# ui.net
KiCad netlist of a schematic drawn in EAGLE
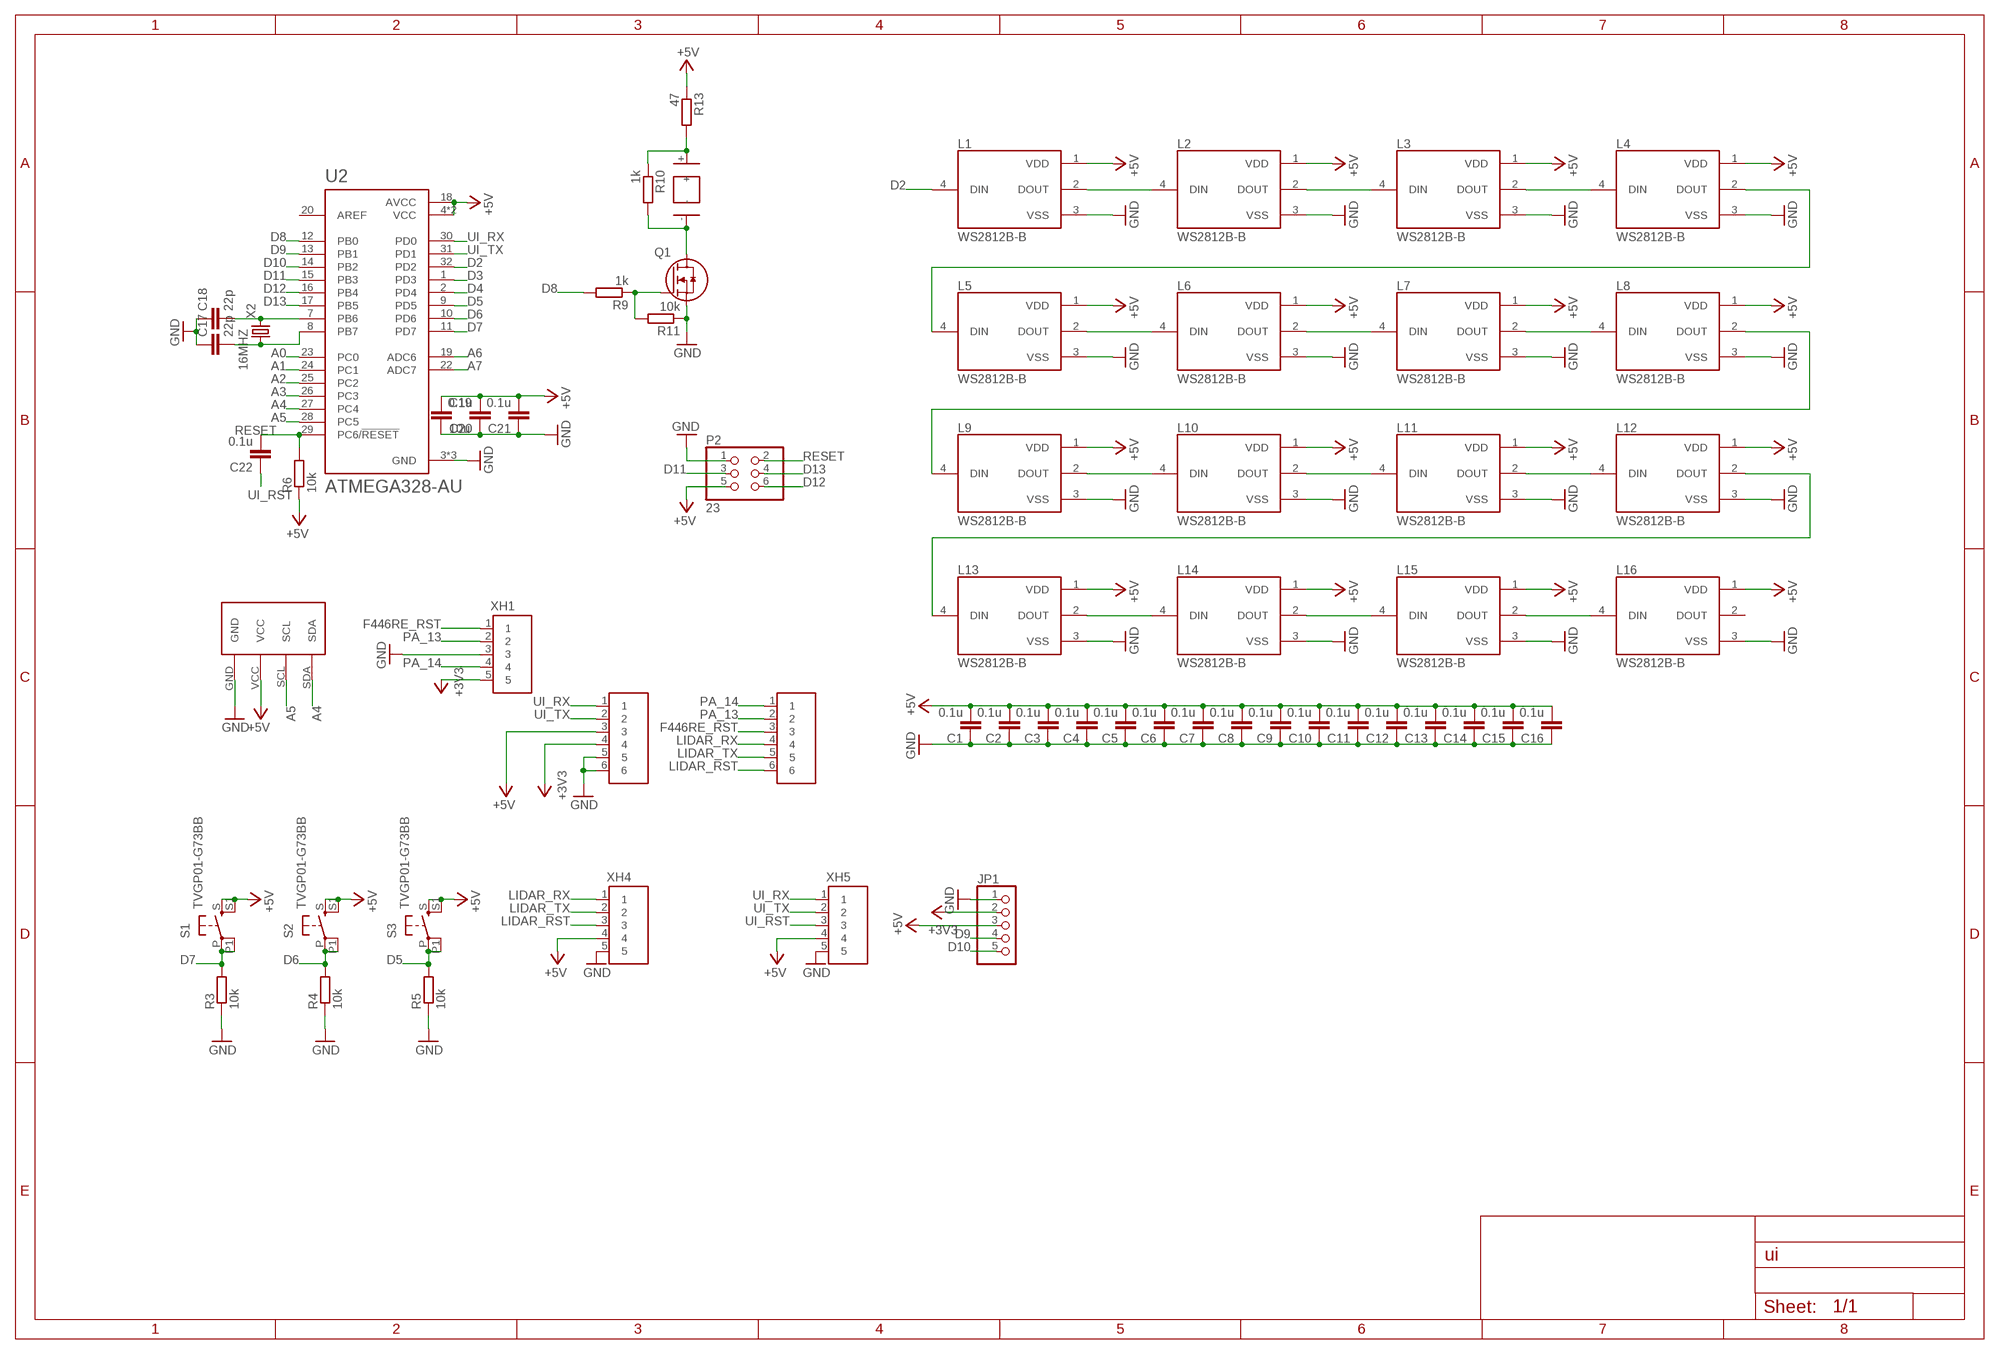
[diagram p0: schematic, sheet 1]

(export (version "E")
  (design (tool "Eeschema 10.0.6"))
  (components
    (comp (ref "B1")
      (value "PKLCS1212E4001-R1")
      (footprint "eagle-import:PKLCS1212E4001-R1")
      (libsource (lib "eagle-import") (part "PKLCS1212E4001-R1"))
    )
    (comp (ref "C1")
      (value "0.1u")
      (footprint "eagle-import:C0603")
      (libsource (lib "eagle-import") (part "C-EUC0603"))
    )
    (comp (ref "C2")
      (value "0.1u")
      (footprint "eagle-import:C0603")
      (libsource (lib "eagle-import") (part "C-EUC0603"))
    )
    (comp (ref "C3")
      (value "0.1u")
      (footprint "eagle-import:C0603")
      (libsource (lib "eagle-import") (part "C-EUC0603"))
    )
    (comp (ref "C4")
      (value "0.1u")
      (footprint "eagle-import:C0603")
      (libsource (lib "eagle-import") (part "C-EUC0603"))
    )
    (comp (ref "C5")
      (value "0.1u")
      (footprint "eagle-import:C0603")
      (libsource (lib "eagle-import") (part "C-EUC0603"))
    )
    (comp (ref "C6")
      (value "0.1u")
      (footprint "eagle-import:C0603")
      (libsource (lib "eagle-import") (part "C-EUC0603"))
    )
    (comp (ref "C7")
      (value "0.1u")
      (footprint "eagle-import:C0603")
      (libsource (lib "eagle-import") (part "C-EUC0603"))
    )
    (comp (ref "C8")
      (value "0.1u")
      (footprint "eagle-import:C0603")
      (libsource (lib "eagle-import") (part "C-EUC0603"))
    )
    (comp (ref "C9")
      (value "0.1u")
      (footprint "eagle-import:C0603")
      (libsource (lib "eagle-import") (part "C-EUC0603"))
    )
    (comp (ref "C10")
      (value "0.1u")
      (footprint "eagle-import:C0603")
      (libsource (lib "eagle-import") (part "C-EUC0603"))
    )
    (comp (ref "C11")
      (value "0.1u")
      (footprint "eagle-import:C0603")
      (libsource (lib "eagle-import") (part "C-EUC0603"))
    )
    (comp (ref "C12")
      (value "0.1u")
      (footprint "eagle-import:C0603")
      (libsource (lib "eagle-import") (part "C-EUC0603"))
    )
    (comp (ref "C13")
      (value "0.1u")
      (footprint "eagle-import:C0603")
      (libsource (lib "eagle-import") (part "C-EUC0603"))
    )
    (comp (ref "C14")
      (value "0.1u")
      (footprint "eagle-import:C0603")
      (libsource (lib "eagle-import") (part "C-EUC0603"))
    )
    (comp (ref "C15")
      (value "0.1u")
      (footprint "eagle-import:C0603")
      (libsource (lib "eagle-import") (part "C-EUC0603"))
    )
    (comp (ref "C16")
      (value "0.1u")
      (footprint "eagle-import:C0603")
      (libsource (lib "eagle-import") (part "C-EUC0603"))
    )
    (comp (ref "C17")
      (value "22p")
      (footprint "eagle-import:C0603")
      (libsource (lib "eagle-import") (part "C-EUC0603"))
    )
    (comp (ref "C18")
      (value "22p")
      (footprint "eagle-import:C0603")
      (libsource (lib "eagle-import") (part "C-EUC0603"))
    )
    (comp (ref "C19")
      (value "10u")
      (footprint "eagle-import:C0805")
      (libsource (lib "eagle-import") (part "C-EUC0805"))
    )
    (comp (ref "C20")
      (value "0.1u")
      (footprint "eagle-import:C0603")
      (libsource (lib "eagle-import") (part "C-EUC0603"))
    )
    (comp (ref "C21")
      (value "0.1u")
      (footprint "eagle-import:C0603")
      (libsource (lib "eagle-import") (part "C-EUC0603"))
    )
    (comp (ref "C22")
      (value "0.1u")
      (footprint "eagle-import:C0603")
      (libsource (lib "eagle-import") (part "C-EUC0603"))
    )
    (comp (ref "JP1")
      (value "PINHD-1X5")
      (footprint "eagle-import:1X05")
      (libsource (lib "eagle-import") (part "PINHD-1X5"))
    )
    (comp (ref "L1")
      (value "WS2812B-B")
      (footprint "eagle-import:LED_WS2812B-B")
      (fields (field (name "MF") "Worldsemi"))
      (libsource (lib "eagle-import") (part "WS2812B-B"))
    )
    (comp (ref "L2")
      (value "WS2812B-B")
      (footprint "eagle-import:LED_WS2812B-B")
      (fields (field (name "MF") "Worldsemi"))
      (libsource (lib "eagle-import") (part "WS2812B-B"))
    )
    (comp (ref "L3")
      (value "WS2812B-B")
      (footprint "eagle-import:LED_WS2812B-B")
      (fields (field (name "MF") "Worldsemi"))
      (libsource (lib "eagle-import") (part "WS2812B-B"))
    )
    (comp (ref "L4")
      (value "WS2812B-B")
      (footprint "eagle-import:LED_WS2812B-B")
      (fields (field (name "MF") "Worldsemi"))
      (libsource (lib "eagle-import") (part "WS2812B-B"))
    )
    (comp (ref "L5")
      (value "WS2812B-B")
      (footprint "eagle-import:LED_WS2812B-B")
      (fields (field (name "MF") "Worldsemi"))
      (libsource (lib "eagle-import") (part "WS2812B-B"))
    )
    (comp (ref "L6")
      (value "WS2812B-B")
      (footprint "eagle-import:LED_WS2812B-B")
      (fields (field (name "MF") "Worldsemi"))
      (libsource (lib "eagle-import") (part "WS2812B-B"))
    )
    (comp (ref "L7")
      (value "WS2812B-B")
      (footprint "eagle-import:LED_WS2812B-B")
      (fields (field (name "MF") "Worldsemi"))
      (libsource (lib "eagle-import") (part "WS2812B-B"))
    )
    (comp (ref "L8")
      (value "WS2812B-B")
      (footprint "eagle-import:LED_WS2812B-B")
      (fields (field (name "MF") "Worldsemi"))
      (libsource (lib "eagle-import") (part "WS2812B-B"))
    )
    (comp (ref "L9")
      (value "WS2812B-B")
      (footprint "eagle-import:LED_WS2812B-B")
      (fields (field (name "MF") "Worldsemi"))
      (libsource (lib "eagle-import") (part "WS2812B-B"))
    )
    (comp (ref "L10")
      (value "WS2812B-B")
      (footprint "eagle-import:LED_WS2812B-B")
      (fields (field (name "MF") "Worldsemi"))
      (libsource (lib "eagle-import") (part "WS2812B-B"))
    )
    (comp (ref "L11")
      (value "WS2812B-B")
      (footprint "eagle-import:LED_WS2812B-B")
      (fields (field (name "MF") "Worldsemi"))
      (libsource (lib "eagle-import") (part "WS2812B-B"))
    )
    (comp (ref "L12")
      (value "WS2812B-B")
      (footprint "eagle-import:LED_WS2812B-B")
      (fields (field (name "MF") "Worldsemi"))
      (libsource (lib "eagle-import") (part "WS2812B-B"))
    )
    (comp (ref "L13")
      (value "WS2812B-B")
      (footprint "eagle-import:LED_WS2812B-B")
      (fields (field (name "MF") "Worldsemi"))
      (libsource (lib "eagle-import") (part "WS2812B-B"))
    )
    (comp (ref "L14")
      (value "WS2812B-B")
      (footprint "eagle-import:LED_WS2812B-B")
      (fields (field (name "MF") "Worldsemi"))
      (libsource (lib "eagle-import") (part "WS2812B-B"))
    )
    (comp (ref "L15")
      (value "WS2812B-B")
      (footprint "eagle-import:LED_WS2812B-B")
      (fields (field (name "MF") "Worldsemi"))
      (libsource (lib "eagle-import") (part "WS2812B-B"))
    )
    (comp (ref "L16")
      (value "WS2812B-B")
      (footprint "eagle-import:LED_WS2812B-B")
      (fields (field (name "MF") "Worldsemi"))
      (libsource (lib "eagle-import") (part "WS2812B-B"))
    )
    (comp (ref "P2") (value "23") (footprint "eagle-import:2_3") (libsource (lib "eagle-import") (part "23")))
    (comp (ref "Q1")
      (value "NP52N06SLG")
      (footprint "eagle-import:TO230P1040X230-3N")
      (libsource (lib "eagle-import") (part "NP52N06SLG"))
    )
    (comp (ref "R3")
      (value "10k")
      (footprint "eagle-import:0204_5")
      (libsource (lib "eagle-import") (part "R-EU_0204/5"))
    )
    (comp (ref "R4")
      (value "10k")
      (footprint "eagle-import:0204_5")
      (libsource (lib "eagle-import") (part "R-EU_0204/5"))
    )
    (comp (ref "R5")
      (value "10k")
      (footprint "eagle-import:0204_5")
      (libsource (lib "eagle-import") (part "R-EU_0204/5"))
    )
    (comp (ref "R6")
      (value "10k")
      (footprint "eagle-import:0204_5")
      (libsource (lib "eagle-import") (part "R-EU_0204/5"))
    )
    (comp (ref "R9")
      (value "1k")
      (footprint "eagle-import:0204_5")
      (libsource (lib "eagle-import") (part "R-EU_0204/5"))
    )
    (comp (ref "R10")
      (value "1k")
      (footprint "eagle-import:0204_5")
      (libsource (lib "eagle-import") (part "R-EU_0204/5"))
    )
    (comp (ref "R11")
      (value "10k")
      (footprint "eagle-import:0204_5")
      (libsource (lib "eagle-import") (part "R-EU_0204/5"))
    )
    (comp (ref "R13")
      (value "47")
      (footprint "eagle-import:0204_5")
      (libsource (lib "eagle-import") (part "R-EU_0204/5"))
    )
    (comp (ref "S1")
      (value "TVGP01-G73BB")
      (footprint "eagle-import:TVGP01-G73BB")
      (libsource (lib "eagle-import") (part "TVGP01-G73BB"))
    )
    (comp (ref "S2")
      (value "TVGP01-G73BB")
      (footprint "eagle-import:TVGP01-G73BB")
      (libsource (lib "eagle-import") (part "TVGP01-G73BB"))
    )
    (comp (ref "S3")
      (value "TVGP01-G73BB")
      (footprint "eagle-import:TVGP01-G73BB")
      (libsource (lib "eagle-import") (part "TVGP01-G73BB"))
    )
    (comp (ref "U1")
      (value "SSD1306")
      (footprint "eagle-import:SSD1306")
      (libsource (lib "eagle-import") (part "SSD1306"))
    )
    (comp (ref "U2")
      (value "ATMEGA328-AU")
      (footprint "eagle-import:QFP80P900X900X120-32N")
      (fields (field (name "MF") "Microchip"))
      (libsource (lib "eagle-import") (part "ATMEGA328-AU"))
    )
    (comp (ref "X2")
      (value "16MHZ")
      (footprint "eagle-import:16MHZ")
      (libsource (lib "eagle-import") (part "16MHZ"))
    )
    (comp (ref "XH1")
      (value "S5B")
      (footprint "eagle-import:S5B")
      (libsource (lib "eagle-import") (part "S5B"))
    )
    (comp (ref "XH2")
      (value "S6B")
      (footprint "eagle-import:S6B")
      (libsource (lib "eagle-import") (part "S6B"))
    )
    (comp (ref "XH3")
      (value "S6B")
      (footprint "eagle-import:S6B")
      (libsource (lib "eagle-import") (part "S6B"))
    )
    (comp (ref "XH4")
      (value "S5B")
      (footprint "eagle-import:S5B")
      (libsource (lib "eagle-import") (part "S5B"))
    )
    (comp (ref "XH5")
      (value "S5B")
      (footprint "eagle-import:S5B")
      (libsource (lib "eagle-import") (part "S5B"))
    )
  )
  (nets
    (net (code "1") (name "+3V3") (class "Default")
      (node (ref "JP1") (pin "2") (pinfunction "2_2") (pintype "passive"))
      (node (ref "XH1") (pin "5") (pinfunction "5_5") (pintype "bidirectional"))
      (node (ref "XH2") (pin "4") (pinfunction "4_4") (pintype "bidirectional"))
    )
    (net (code "2") (name "+5V") (class "Default")
      (node (ref "C1") (pin "2") (pinfunction "2_2") (pintype "passive"))
      (node (ref "C10") (pin "2") (pinfunction "2_2") (pintype "passive"))
      (node (ref "C11") (pin "2") (pinfunction "2_2") (pintype "passive"))
      (node (ref "C12") (pin "2") (pinfunction "2_2") (pintype "passive"))
      (node (ref "C13") (pin "2") (pinfunction "2_2") (pintype "passive"))
      (node (ref "C14") (pin "2") (pinfunction "2_2") (pintype "passive"))
      (node (ref "C15") (pin "2") (pinfunction "2_2") (pintype "passive"))
      (node (ref "C16") (pin "2") (pinfunction "2_2") (pintype "passive"))
      (node (ref "C19") (pin "1") (pinfunction "1_1") (pintype "passive"))
      (node (ref "C2") (pin "2") (pinfunction "2_2") (pintype "passive"))
      (node (ref "C20") (pin "2") (pinfunction "2_2") (pintype "passive"))
      (node (ref "C21") (pin "2") (pinfunction "2_2") (pintype "passive"))
      (node (ref "C3") (pin "2") (pinfunction "2_2") (pintype "passive"))
      (node (ref "C4") (pin "2") (pinfunction "2_2") (pintype "passive"))
      (node (ref "C5") (pin "2") (pinfunction "2_2") (pintype "passive"))
      (node (ref "C6") (pin "2") (pinfunction "2_2") (pintype "passive"))
      (node (ref "C7") (pin "2") (pinfunction "2_2") (pintype "passive"))
      (node (ref "C8") (pin "2") (pinfunction "2_2") (pintype "passive"))
      (node (ref "C9") (pin "2") (pinfunction "2_2") (pintype "passive"))
      (node (ref "JP1") (pin "3") (pinfunction "3_3") (pintype "passive"))
      (node (ref "L1") (pin "1") (pinfunction "VDD_1") (pintype "power_in"))
      (node (ref "L10") (pin "1") (pinfunction "VDD_1") (pintype "power_in"))
      (node (ref "L11") (pin "1") (pinfunction "VDD_1") (pintype "power_in"))
      (node (ref "L12") (pin "1") (pinfunction "VDD_1") (pintype "power_in"))
      (node (ref "L13") (pin "1") (pinfunction "VDD_1") (pintype "power_in"))
      (node (ref "L14") (pin "1") (pinfunction "VDD_1") (pintype "power_in"))
      (node (ref "L15") (pin "1") (pinfunction "VDD_1") (pintype "power_in"))
      (node (ref "L16") (pin "1") (pinfunction "VDD_1") (pintype "power_in"))
      (node (ref "L2") (pin "1") (pinfunction "VDD_1") (pintype "power_in"))
      (node (ref "L3") (pin "1") (pinfunction "VDD_1") (pintype "power_in"))
      (node (ref "L4") (pin "1") (pinfunction "VDD_1") (pintype "power_in"))
      (node (ref "L5") (pin "1") (pinfunction "VDD_1") (pintype "power_in"))
      (node (ref "L6") (pin "1") (pinfunction "VDD_1") (pintype "power_in"))
      (node (ref "L7") (pin "1") (pinfunction "VDD_1") (pintype "power_in"))
      (node (ref "L8") (pin "1") (pinfunction "VDD_1") (pintype "power_in"))
      (node (ref "L9") (pin "1") (pinfunction "VDD_1") (pintype "power_in"))
      (node (ref "P2") (pin "5") (pinfunction "5_5") (pintype "passive"))
      (node (ref "R13") (pin "1") (pinfunction "1_1") (pintype "passive"))
      (node (ref "R6") (pin "1") (pinfunction "1_1") (pintype "passive"))
      (node (ref "S1") (pin "S") (pinfunction "S_S") (pintype "passive"))
      (node (ref "S1") (pin "S1") (pinfunction "S1_S1") (pintype "passive"))
      (node (ref "S2") (pin "S") (pinfunction "S_S") (pintype "passive"))
      (node (ref "S2") (pin "S1") (pinfunction "S1_S1") (pintype "passive"))
      (node (ref "S3") (pin "S") (pinfunction "S_S") (pintype "passive"))
      (node (ref "S3") (pin "S1") (pinfunction "S1_S1") (pintype "passive"))
      (node (ref "U1") (pin "VCC") (pinfunction "VCC_VCC") (pintype "bidirectional"))
      (node (ref "U2") (pin "18") (pinfunction "AVCC_18") (pintype "power_in"))
      (node (ref "U2") (pin "4") (pinfunction "VCC_4") (pintype "power_in"))
      (node (ref "U2") (pin "6") (pinfunction "VCC_6") (pintype "power_in"))
      (node (ref "XH2") (pin "3") (pinfunction "3_3") (pintype "bidirectional"))
      (node (ref "XH4") (pin "4") (pinfunction "4_4") (pintype "bidirectional"))
      (node (ref "XH5") (pin "4") (pinfunction "4_4") (pintype "bidirectional"))
    )
    (net (code "3") (name "/A0") (class "Default")
      (node (ref "U2") (pin "23") (pinfunction "PC0_23") (pintype "bidirectional"))
    )
    (net (code "4") (name "/A1") (class "Default")
      (node (ref "U2") (pin "24") (pinfunction "PC1_24") (pintype "bidirectional"))
    )
    (net (code "5") (name "/A2") (class "Default")
      (node (ref "U2") (pin "25") (pinfunction "PC2_25") (pintype "bidirectional"))
    )
    (net (code "6") (name "/A3") (class "Default")
      (node (ref "U2") (pin "26") (pinfunction "PC3_26") (pintype "bidirectional"))
    )
    (net (code "7") (name "/A4") (class "Default")
      (node (ref "U1") (pin "SDA") (pinfunction "SDA_SDA") (pintype "bidirectional"))
      (node (ref "U2") (pin "27") (pinfunction "PC4_27") (pintype "bidirectional"))
    )
    (net (code "8") (name "/A5") (class "Default")
      (node (ref "U1") (pin "SCL") (pinfunction "SCL_SCL") (pintype "bidirectional"))
      (node (ref "U2") (pin "28") (pinfunction "PC5_28") (pintype "bidirectional"))
    )
    (net (code "9") (name "/A6") (class "Default")
      (node (ref "U2") (pin "19") (pinfunction "ADC6_19") (pintype "bidirectional"))
    )
    (net (code "10") (name "/A7") (class "Default")
      (node (ref "U2") (pin "22") (pinfunction "ADC7_22") (pintype "bidirectional"))
    )
    (net (code "11") (name "/D2") (class "Default")
      (node (ref "L1") (pin "4") (pinfunction "DIN_4") (pintype "input"))
      (node (ref "U2") (pin "32") (pinfunction "PD2_32") (pintype "bidirectional"))
    )
    (net (code "12") (name "/D3") (class "Default")
      (node (ref "U2") (pin "1") (pinfunction "PD3_1") (pintype "bidirectional"))
    )
    (net (code "13") (name "/D4") (class "Default")
      (node (ref "U2") (pin "2") (pinfunction "PD4_2") (pintype "bidirectional"))
    )
    (net (code "14") (name "/D5") (class "Default")
      (node (ref "R5") (pin "2") (pinfunction "2_2") (pintype "passive"))
      (node (ref "S3") (pin "P") (pinfunction "P_P") (pintype "passive"))
      (node (ref "S3") (pin "P1") (pinfunction "P1_P1") (pintype "passive"))
      (node (ref "U2") (pin "9") (pinfunction "PD5_9") (pintype "bidirectional"))
    )
    (net (code "15") (name "/D6") (class "Default")
      (node (ref "R4") (pin "2") (pinfunction "2_2") (pintype "passive"))
      (node (ref "S2") (pin "P") (pinfunction "P_P") (pintype "passive"))
      (node (ref "S2") (pin "P1") (pinfunction "P1_P1") (pintype "passive"))
      (node (ref "U2") (pin "10") (pinfunction "PD6_10") (pintype "bidirectional"))
    )
    (net (code "16") (name "/D7") (class "Default")
      (node (ref "R3") (pin "2") (pinfunction "2_2") (pintype "passive"))
      (node (ref "S1") (pin "P") (pinfunction "P_P") (pintype "passive"))
      (node (ref "S1") (pin "P1") (pinfunction "P1_P1") (pintype "passive"))
      (node (ref "U2") (pin "11") (pinfunction "PD7_11") (pintype "bidirectional"))
    )
    (net (code "17") (name "/D8") (class "Default")
      (node (ref "R9") (pin "2") (pinfunction "2_2") (pintype "passive"))
      (node (ref "U2") (pin "12") (pinfunction "PB0_12") (pintype "bidirectional"))
    )
    (net (code "18") (name "/D9") (class "Default")
      (node (ref "JP1") (pin "4") (pinfunction "4_4") (pintype "passive"))
      (node (ref "U2") (pin "13") (pinfunction "PB1_13") (pintype "bidirectional"))
    )
    (net (code "19") (name "/D10") (class "Default")
      (node (ref "JP1") (pin "5") (pinfunction "5_5") (pintype "passive"))
      (node (ref "U2") (pin "14") (pinfunction "PB2_14") (pintype "bidirectional"))
    )
    (net (code "20") (name "/D11") (class "Default")
      (node (ref "P2") (pin "3") (pinfunction "3_3") (pintype "passive"))
      (node (ref "U2") (pin "15") (pinfunction "PB3_15") (pintype "bidirectional"))
    )
    (net (code "21") (name "/D12") (class "Default")
      (node (ref "P2") (pin "6") (pinfunction "6_6") (pintype "passive"))
      (node (ref "U2") (pin "16") (pinfunction "PB4_16") (pintype "bidirectional"))
    )
    (net (code "22") (name "/D13") (class "Default")
      (node (ref "P2") (pin "4") (pinfunction "4_4") (pintype "passive"))
      (node (ref "U2") (pin "17") (pinfunction "PB5_17") (pintype "bidirectional"))
    )
    (net (code "23") (name "/F446RE_RST") (class "Default")
      (node (ref "XH1") (pin "1") (pinfunction "1_1") (pintype "bidirectional"))
      (node (ref "XH3") (pin "3") (pinfunction "3_3") (pintype "bidirectional"))
    )
    (net (code "24") (name "/LIDAR_RST") (class "Default")
      (node (ref "XH3") (pin "6") (pinfunction "6_6") (pintype "bidirectional"))
      (node (ref "XH4") (pin "3") (pinfunction "3_3") (pintype "bidirectional"))
    )
    (net (code "25") (name "/LIDAR_RX") (class "Default")
      (node (ref "XH3") (pin "4") (pinfunction "4_4") (pintype "bidirectional"))
      (node (ref "XH4") (pin "1") (pinfunction "1_1") (pintype "bidirectional"))
    )
    (net (code "26") (name "/LIDAR_TX") (class "Default")
      (node (ref "XH3") (pin "5") (pinfunction "5_5") (pintype "bidirectional"))
      (node (ref "XH4") (pin "2") (pinfunction "2_2") (pintype "bidirectional"))
    )
    (net (code "27") (name "/PA_13") (class "Default")
      (node (ref "XH1") (pin "2") (pinfunction "2_2") (pintype "bidirectional"))
      (node (ref "XH3") (pin "2") (pinfunction "2_2") (pintype "bidirectional"))
    )
    (net (code "28") (name "/PA_14") (class "Default")
      (node (ref "XH1") (pin "4") (pinfunction "4_4") (pintype "bidirectional"))
      (node (ref "XH3") (pin "1") (pinfunction "1_1") (pintype "bidirectional"))
    )
    (net (code "29") (name "/RESET") (class "Default")
      (node (ref "C22") (pin "2") (pinfunction "2_2") (pintype "passive"))
      (node (ref "P2") (pin "2") (pinfunction "2_2") (pintype "passive"))
      (node (ref "R6") (pin "2") (pinfunction "2_2") (pintype "passive"))
      (node (ref "U2") (pin "29") (pinfunction "PC6/~{RESET}_29") (pintype "bidirectional"))
    )
    (net (code "30") (name "/UI_RST") (class "Default")
      (node (ref "C22") (pin "1") (pinfunction "1_1") (pintype "passive"))
      (node (ref "XH5") (pin "3") (pinfunction "3_3") (pintype "bidirectional"))
    )
    (net (code "31") (name "/UI_RX") (class "Default")
      (node (ref "U2") (pin "30") (pinfunction "PD0_30") (pintype "bidirectional"))
      (node (ref "XH2") (pin "1") (pinfunction "1_1") (pintype "bidirectional"))
      (node (ref "XH5") (pin "1") (pinfunction "1_1") (pintype "bidirectional"))
    )
    (net (code "32") (name "/UI_TX") (class "Default")
      (node (ref "U2") (pin "31") (pinfunction "PD1_31") (pintype "bidirectional"))
      (node (ref "XH2") (pin "2") (pinfunction "2_2") (pintype "bidirectional"))
      (node (ref "XH5") (pin "2") (pinfunction "2_2") (pintype "bidirectional"))
    )
    (net (code "33") (name "GND") (class "Default")
      (node (ref "C1") (pin "1") (pinfunction "1_1") (pintype "passive"))
      (node (ref "C10") (pin "1") (pinfunction "1_1") (pintype "passive"))
      (node (ref "C11") (pin "1") (pinfunction "1_1") (pintype "passive"))
      (node (ref "C12") (pin "1") (pinfunction "1_1") (pintype "passive"))
      (node (ref "C13") (pin "1") (pinfunction "1_1") (pintype "passive"))
      (node (ref "C14") (pin "1") (pinfunction "1_1") (pintype "passive"))
      (node (ref "C15") (pin "1") (pinfunction "1_1") (pintype "passive"))
      (node (ref "C16") (pin "1") (pinfunction "1_1") (pintype "passive"))
      (node (ref "C17") (pin "1") (pinfunction "1_1") (pintype "passive"))
      (node (ref "C18") (pin "1") (pinfunction "1_1") (pintype "passive"))
      (node (ref "C19") (pin "2") (pinfunction "2_2") (pintype "passive"))
      (node (ref "C2") (pin "1") (pinfunction "1_1") (pintype "passive"))
      (node (ref "C20") (pin "1") (pinfunction "1_1") (pintype "passive"))
      (node (ref "C21") (pin "1") (pinfunction "1_1") (pintype "passive"))
      (node (ref "C3") (pin "1") (pinfunction "1_1") (pintype "passive"))
      (node (ref "C4") (pin "1") (pinfunction "1_1") (pintype "passive"))
      (node (ref "C5") (pin "1") (pinfunction "1_1") (pintype "passive"))
      (node (ref "C6") (pin "1") (pinfunction "1_1") (pintype "passive"))
      (node (ref "C7") (pin "1") (pinfunction "1_1") (pintype "passive"))
      (node (ref "C8") (pin "1") (pinfunction "1_1") (pintype "passive"))
      (node (ref "C9") (pin "1") (pinfunction "1_1") (pintype "passive"))
      (node (ref "JP1") (pin "1") (pinfunction "1_1") (pintype "passive"))
      (node (ref "L1") (pin "3") (pinfunction "VSS_3") (pintype "power_in"))
      (node (ref "L10") (pin "3") (pinfunction "VSS_3") (pintype "power_in"))
      (node (ref "L11") (pin "3") (pinfunction "VSS_3") (pintype "power_in"))
      (node (ref "L12") (pin "3") (pinfunction "VSS_3") (pintype "power_in"))
      (node (ref "L13") (pin "3") (pinfunction "VSS_3") (pintype "power_in"))
      (node (ref "L14") (pin "3") (pinfunction "VSS_3") (pintype "power_in"))
      (node (ref "L15") (pin "3") (pinfunction "VSS_3") (pintype "power_in"))
      (node (ref "L16") (pin "3") (pinfunction "VSS_3") (pintype "power_in"))
      (node (ref "L2") (pin "3") (pinfunction "VSS_3") (pintype "power_in"))
      (node (ref "L3") (pin "3") (pinfunction "VSS_3") (pintype "power_in"))
      (node (ref "L4") (pin "3") (pinfunction "VSS_3") (pintype "power_in"))
      (node (ref "L5") (pin "3") (pinfunction "VSS_3") (pintype "power_in"))
      (node (ref "L6") (pin "3") (pinfunction "VSS_3") (pintype "power_in"))
      (node (ref "L7") (pin "3") (pinfunction "VSS_3") (pintype "power_in"))
      (node (ref "L8") (pin "3") (pinfunction "VSS_3") (pintype "power_in"))
      (node (ref "L9") (pin "3") (pinfunction "VSS_3") (pintype "power_in"))
      (node (ref "P2") (pin "1") (pinfunction "1_1") (pintype "passive"))
      (node (ref "Q1") (pin "S") (pinfunction "S_S") (pintype "passive"))
      (node (ref "R11") (pin "1") (pinfunction "1_1") (pintype "passive"))
      (node (ref "R3") (pin "1") (pinfunction "1_1") (pintype "passive"))
      (node (ref "R4") (pin "1") (pinfunction "1_1") (pintype "passive"))
      (node (ref "R5") (pin "1") (pinfunction "1_1") (pintype "passive"))
      (node (ref "U1") (pin "GND") (pinfunction "GND_GND") (pintype "bidirectional"))
      (node (ref "U2") (pin "21") (pinfunction "GND_21") (pintype "power_in"))
      (node (ref "U2") (pin "3") (pinfunction "GND_3") (pintype "power_in"))
      (node (ref "U2") (pin "5") (pinfunction "GND_5") (pintype "power_in"))
      (node (ref "XH1") (pin "3") (pinfunction "3_3") (pintype "bidirectional"))
      (node (ref "XH2") (pin "5") (pinfunction "5_5") (pintype "bidirectional"))
      (node (ref "XH2") (pin "6") (pinfunction "6_6") (pintype "bidirectional"))
      (node (ref "XH4") (pin "5") (pinfunction "5_5") (pintype "bidirectional"))
      (node (ref "XH5") (pin "5") (pinfunction "5_5") (pintype "bidirectional"))
    )
    (net (code "34") (name "Net-(B1-Pad+)") (class "Default")
      (node (ref "B1") (pin "+") (pinfunction "+_+") (pintype "bidirectional"))
      (node (ref "R10") (pin "1") (pinfunction "1_1") (pintype "passive"))
      (node (ref "R13") (pin "2") (pinfunction "2_2") (pintype "passive"))
    )
    (net (code "35") (name "Net-(B1-Pad-)") (class "Default")
      (node (ref "B1") (pin "-") (pinfunction "-_-") (pintype "bidirectional"))
      (node (ref "Q1") (pin "D") (pinfunction "D_D") (pintype "passive"))
      (node (ref "R10") (pin "2") (pinfunction "2_2") (pintype "passive"))
    )
    (net (code "36") (name "Net-(L1-DOUT)") (class "Default")
      (node (ref "L1") (pin "2") (pinfunction "DOUT_2") (pintype "output"))
      (node (ref "L2") (pin "4") (pinfunction "DIN_4") (pintype "input"))
    )
    (net (code "37") (name "Net-(L2-DOUT)") (class "Default")
      (node (ref "L2") (pin "2") (pinfunction "DOUT_2") (pintype "output"))
      (node (ref "L3") (pin "4") (pinfunction "DIN_4") (pintype "input"))
    )
    (net (code "38") (name "Net-(L3-DOUT)") (class "Default")
      (node (ref "L3") (pin "2") (pinfunction "DOUT_2") (pintype "output"))
      (node (ref "L4") (pin "4") (pinfunction "DIN_4") (pintype "input"))
    )
    (net (code "39") (name "Net-(L4-DOUT)") (class "Default")
      (node (ref "L4") (pin "2") (pinfunction "DOUT_2") (pintype "output"))
      (node (ref "L5") (pin "4") (pinfunction "DIN_4") (pintype "input"))
    )
    (net (code "40") (name "Net-(L5-DOUT)") (class "Default")
      (node (ref "L5") (pin "2") (pinfunction "DOUT_2") (pintype "output"))
      (node (ref "L6") (pin "4") (pinfunction "DIN_4") (pintype "input"))
    )
    (net (code "41") (name "Net-(L6-DOUT)") (class "Default")
      (node (ref "L6") (pin "2") (pinfunction "DOUT_2") (pintype "output"))
      (node (ref "L7") (pin "4") (pinfunction "DIN_4") (pintype "input"))
    )
    (net (code "42") (name "Net-(L7-DOUT)") (class "Default")
      (node (ref "L7") (pin "2") (pinfunction "DOUT_2") (pintype "output"))
      (node (ref "L8") (pin "4") (pinfunction "DIN_4") (pintype "input"))
    )
    (net (code "43") (name "Net-(L8-DOUT)") (class "Default")
      (node (ref "L8") (pin "2") (pinfunction "DOUT_2") (pintype "output"))
      (node (ref "L9") (pin "4") (pinfunction "DIN_4") (pintype "input"))
    )
    (net (code "44") (name "Net-(L10-DIN)") (class "Default")
      (node (ref "L10") (pin "4") (pinfunction "DIN_4") (pintype "input"))
      (node (ref "L9") (pin "2") (pinfunction "DOUT_2") (pintype "output"))
    )
    (net (code "45") (name "Net-(L10-DOUT)") (class "Default")
      (node (ref "L10") (pin "2") (pinfunction "DOUT_2") (pintype "output"))
      (node (ref "L11") (pin "4") (pinfunction "DIN_4") (pintype "input"))
    )
    (net (code "46") (name "Net-(L11-DOUT)") (class "Default")
      (node (ref "L11") (pin "2") (pinfunction "DOUT_2") (pintype "output"))
      (node (ref "L12") (pin "4") (pinfunction "DIN_4") (pintype "input"))
    )
    (net (code "47") (name "Net-(L12-DOUT)") (class "Default")
      (node (ref "L12") (pin "2") (pinfunction "DOUT_2") (pintype "output"))
      (node (ref "L13") (pin "4") (pinfunction "DIN_4") (pintype "input"))
    )
    (net (code "48") (name "Net-(L13-DOUT)") (class "Default")
      (node (ref "L13") (pin "2") (pinfunction "DOUT_2") (pintype "output"))
      (node (ref "L14") (pin "4") (pinfunction "DIN_4") (pintype "input"))
    )
    (net (code "49") (name "Net-(L14-DOUT)") (class "Default")
      (node (ref "L14") (pin "2") (pinfunction "DOUT_2") (pintype "output"))
      (node (ref "L15") (pin "4") (pinfunction "DIN_4") (pintype "input"))
    )
    (net (code "50") (name "Net-(L15-DOUT)") (class "Default")
      (node (ref "L15") (pin "2") (pinfunction "DOUT_2") (pintype "output"))
      (node (ref "L16") (pin "4") (pinfunction "DIN_4") (pintype "input"))
    )
    (net (code "51") (name "Net-(Q1-PadG)") (class "Default")
      (node (ref "Q1") (pin "G") (pinfunction "G_G") (pintype "passive"))
      (node (ref "R11") (pin "2") (pinfunction "2_2") (pintype "passive"))
      (node (ref "R9") (pin "1") (pinfunction "1_1") (pintype "passive"))
    )
    (net (code "52") (name "Net-(U2-PB6)") (class "Default")
      (node (ref "C18") (pin "2") (pinfunction "2_2") (pintype "passive"))
      (node (ref "U2") (pin "7") (pinfunction "PB6_7") (pintype "bidirectional"))
      (node (ref "X2") (pin "P$2") (pinfunction "2_P$2") (pintype "passive"))
    )
    (net (code "53") (name "Net-(U2-PB7)") (class "Default")
      (node (ref "C17") (pin "2") (pinfunction "2_2") (pintype "passive"))
      (node (ref "U2") (pin "8") (pinfunction "PB7_8") (pintype "bidirectional"))
      (node (ref "X2") (pin "P$1") (pinfunction "1_P$1") (pintype "passive"))
    )
    (net (code "54") (name "unconnected-(L16-DOUT-Pad2)") (class "Default")
      (node (ref "L16") (pin "2") (pinfunction "DOUT_2") (pintype "output"))
    )
    (net (code "55") (name "unconnected-(U2-AREF-Pad20)") (class "Default")
      (node (ref "U2") (pin "20") (pinfunction "AREF_20") (pintype "input"))
    )
  )
)
